# WH_Test_Station_Schematic_RevA.net
KiCad netlist of a schematic drawn in EasyEDA
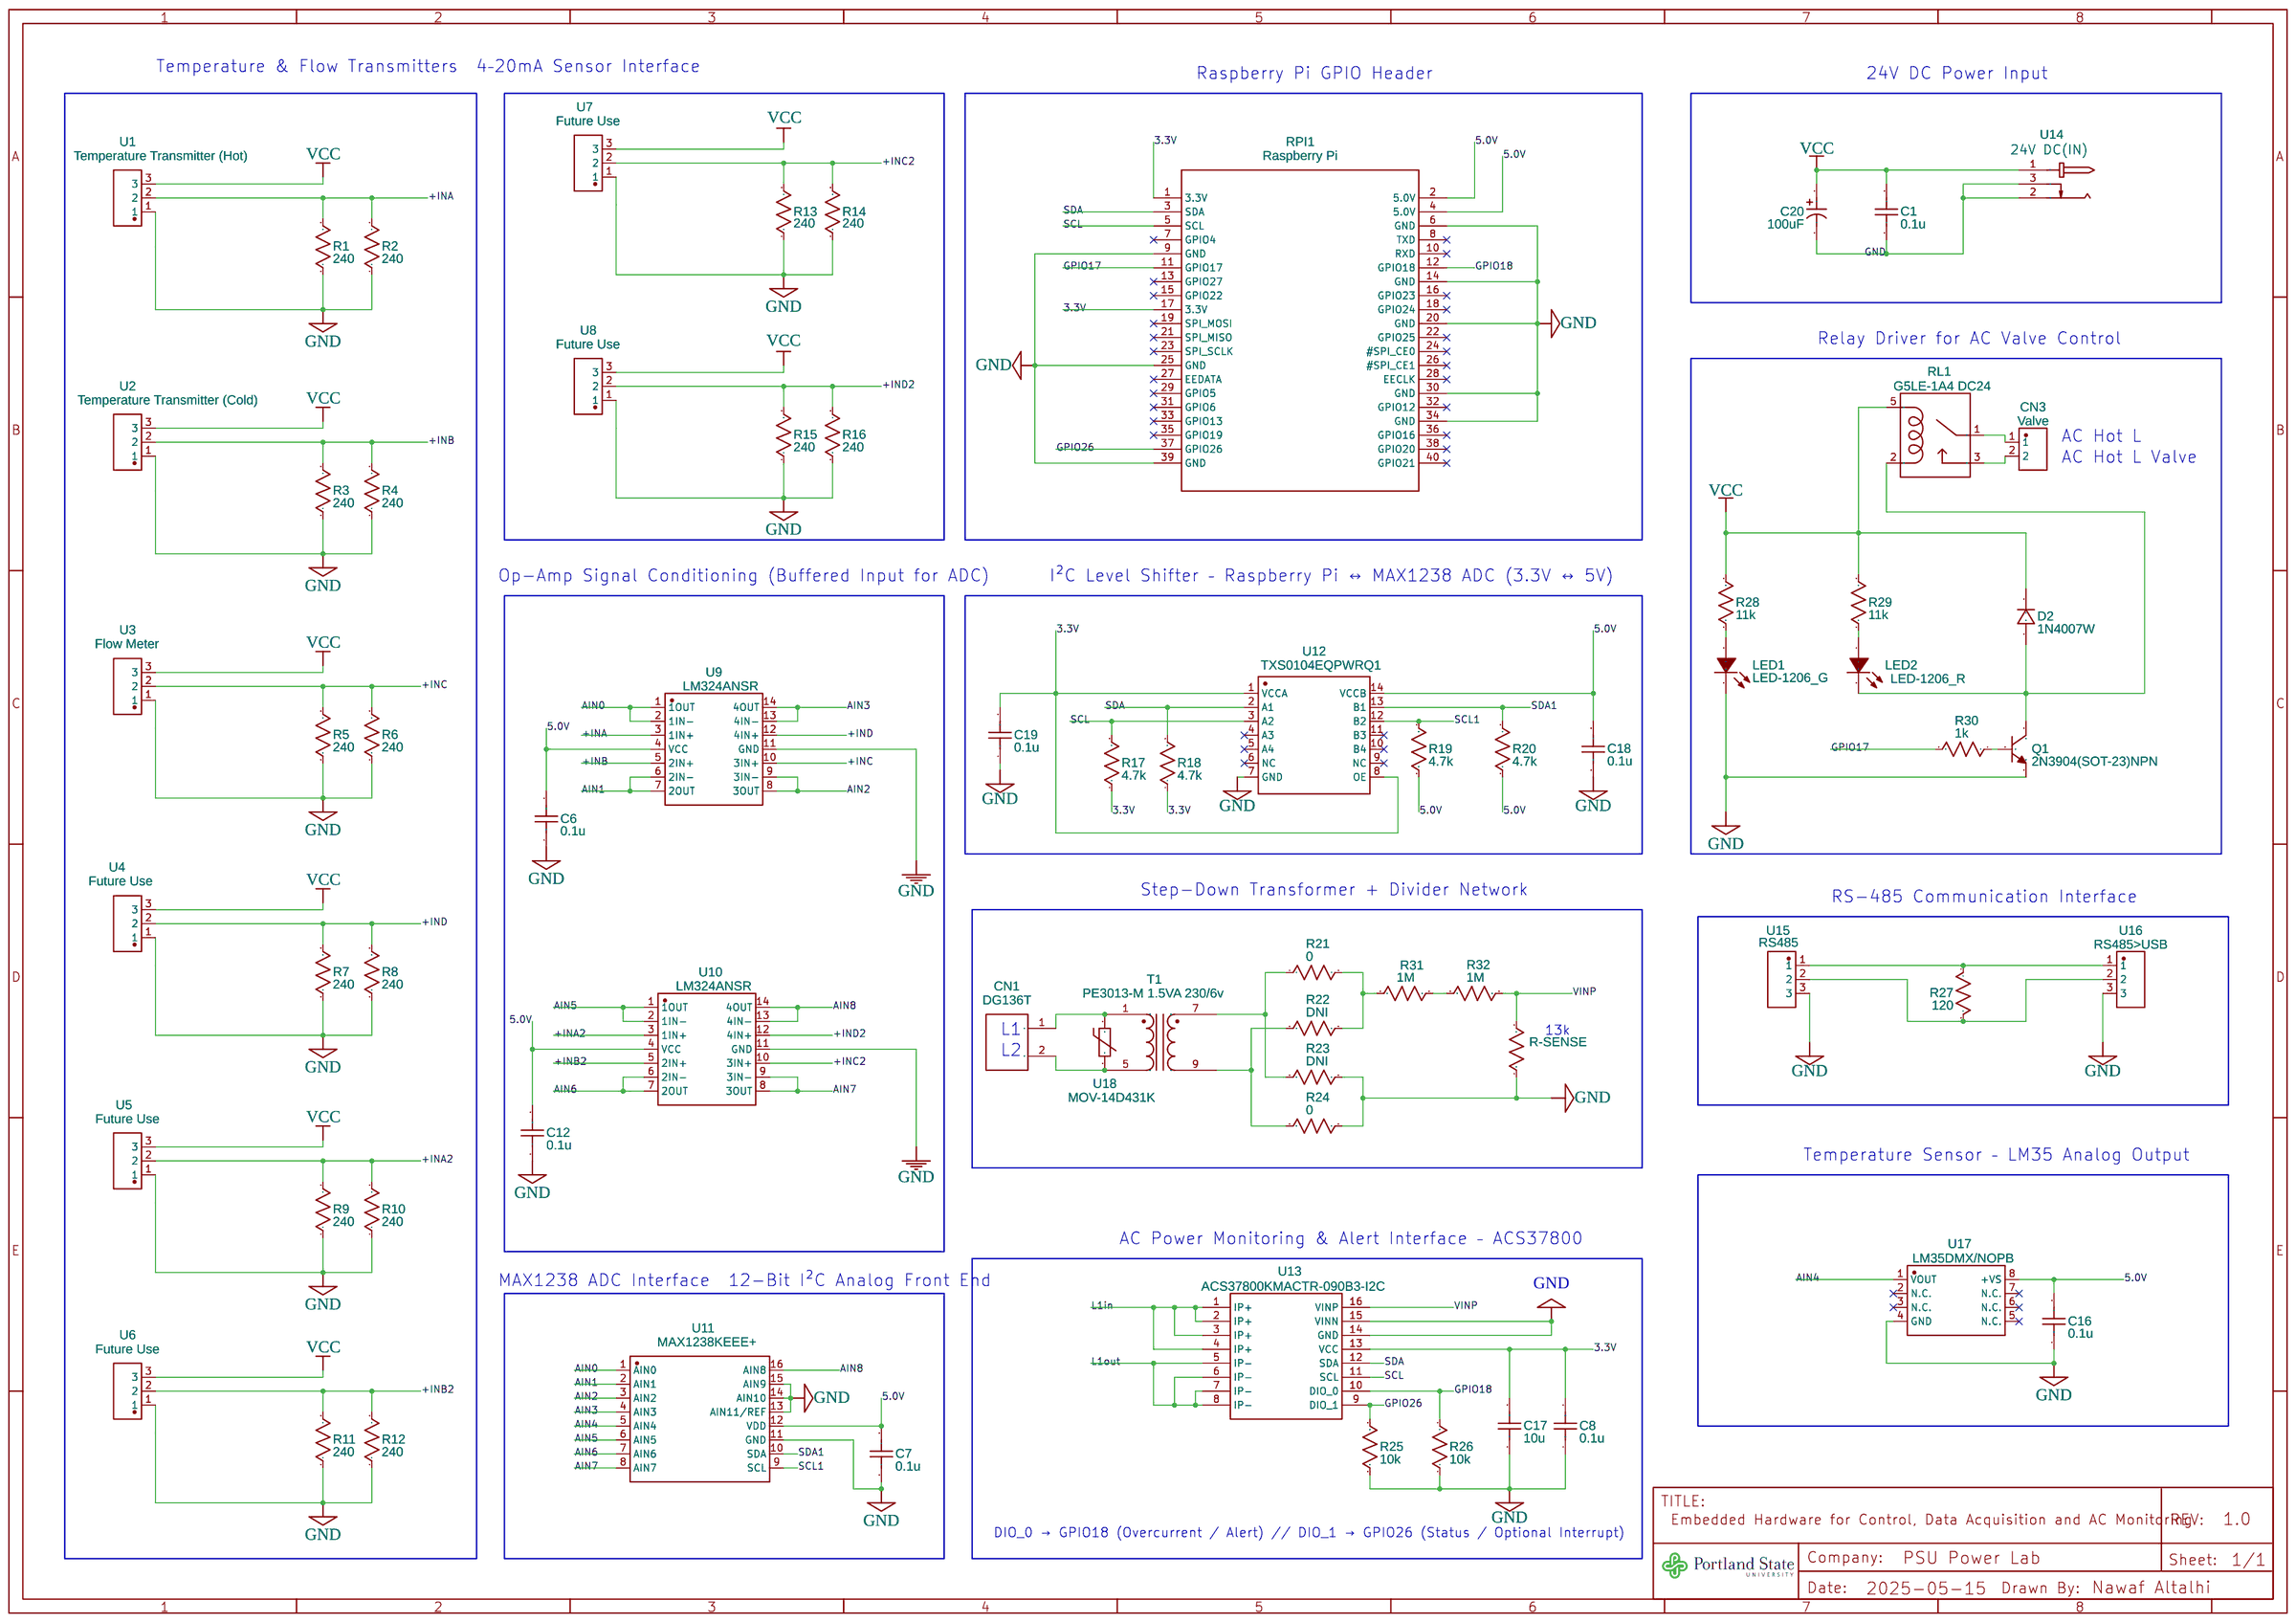
[diagram p0: schematic sheet]

(export (version "E")
  (design (tool "Eeschema 10.0.6"))
  (components
    (comp (ref "C1") (value "0.1u") (libsource (lib "") (part "C_0603_US")))
    (comp (ref "C6") (value "0.1u") (libsource (lib "") (part "C_0603_US")))
    (comp (ref "C7") (value "0.1u") (libsource (lib "") (part "C_0603_US")))
    (comp (ref "C8") (value "0.1u") (libsource (lib "") (part "C_0603_US")))
    (comp (ref "C12") (value "0.1u") (libsource (lib "") (part "C_0603_US")))
    (comp (ref "C16") (value "0.1u") (libsource (lib "") (part "C_0603_US")))
    (comp (ref "C17") (value "10u") (libsource (lib "") (part "C_0603_US")))
    (comp (ref "C18") (value "0.1u") (libsource (lib "") (part "C_0603_US")))
    (comp (ref "C19") (value "0.1u") (libsource (lib "") (part "C_0603_US")))
    (comp (ref "C20")
      (value "100uF")
      (fields (field (name "Manufacturer Part") "RVT1H101M0607") (field (name "Manufacturer") "ROQANG(容强)"))
      (libsource (lib "") (part "RVT1H101M0607"))
    )
    (comp (ref "CN1")
      (value "DG136T")
      (fields (field (name "Manufacturer Part") "Degson"))
      (libsource (lib "") (part "DG136T_2W_x12.7_Terminals"))
    )
    (comp (ref "CN3")
      (value "Valve")
      (fields
        (field (name "Manufacturer Part") "DBT50G-6.35-2P-BK-P OGC")
        (field (name "Manufacturer") "DORABO(地博电气)")
      )
      (libsource (lib "") (part "DBT50G-6.35-2P-BK-P OGC"))
    )
    (comp (ref "D2")
      (value "1N4007W")
      (fields (field (name "Manufacturer") "BLUE ROCKET"))
      (libsource (lib "") (part "1N4007W"))
    )
    (comp (ref "LED1")
      (value "LED-1206_G")
      (fields
        (field (name "Manufacturer Part") "19-217/GHC-YR1S2/3T")
        (field (name "Manufacturer") "EVERLIGHT(台湾亿光)")
      )
      (libsource (lib "") (part "LED-0603_G"))
    )
    (comp (ref "LED2")
      (value "LED-1206_R")
      (fields
        (field (name "Manufacturer Part") "19-217/R6C-AL1M2VY/3T")
        (field (name "Manufacturer") "EVERLIGHT(台湾亿光)")
      )
      (libsource (lib "") (part "LED-0603_R"))
    )
    (comp (ref "Q1")
      (value "2N3904(SOT-23)NPN")
      (fields (field (name "Manufacturer Part") "2n3904S-RTK/PS") (field (name "Manufacturer") "KEC"))
      (libsource (lib "") (part "2N3904(SOT-23)"))
    )
    (comp (ref "R-SENSE") (value "13k") (libsource (lib "") (part "R_0603_US_2")))
    (comp (ref "R1") (value "240") (libsource (lib "") (part "R_0603_US")))
    (comp (ref "R2") (value "240") (libsource (lib "") (part "R_0603_US")))
    (comp (ref "R3") (value "240") (libsource (lib "") (part "R_0603_US")))
    (comp (ref "R4") (value "240") (libsource (lib "") (part "R_0603_US")))
    (comp (ref "R5") (value "240") (libsource (lib "") (part "R_0603_US")))
    (comp (ref "R6") (value "240") (libsource (lib "") (part "R_0603_US")))
    (comp (ref "R7") (value "240") (libsource (lib "") (part "R_0603_US")))
    (comp (ref "R8") (value "240") (libsource (lib "") (part "R_0603_US")))
    (comp (ref "R9") (value "240") (libsource (lib "") (part "R_0603_US")))
    (comp (ref "R10") (value "240") (libsource (lib "") (part "R_0603_US")))
    (comp (ref "R11") (value "240") (libsource (lib "") (part "R_0603_US")))
    (comp (ref "R12") (value "240") (libsource (lib "") (part "R_0603_US")))
    (comp (ref "R13") (value "240") (libsource (lib "") (part "R_0603_US")))
    (comp (ref "R14") (value "240") (libsource (lib "") (part "R_0603_US")))
    (comp (ref "R15") (value "240") (libsource (lib "") (part "R_0603_US")))
    (comp (ref "R16") (value "240") (libsource (lib "") (part "R_0603_US")))
    (comp (ref "R17") (value "4.7k") (libsource (lib "") (part "R_0603_US")))
    (comp (ref "R18") (value "4.7k") (libsource (lib "") (part "R_0603_US")))
    (comp (ref "R19") (value "4.7k") (libsource (lib "") (part "R_0603_US")))
    (comp (ref "R20") (value "4.7k") (libsource (lib "") (part "R_0603_US")))
    (comp (ref "R21") (value "0") (libsource (lib "") (part "R_0603_US_1")))
    (comp (ref "R22") (value "DNI") (libsource (lib "") (part "R_0603_US_1")))
    (comp (ref "R23") (value "DNI") (libsource (lib "") (part "R_0603_US_1")))
    (comp (ref "R24") (value "0") (libsource (lib "") (part "R_0603_US_1")))
    (comp (ref "R25") (value "10k") (libsource (lib "") (part "R_0603_US")))
    (comp (ref "R26") (value "10k") (libsource (lib "") (part "R_0603_US")))
    (comp (ref "R27") (value "120") (libsource (lib "") (part "R_0603_US_3")))
    (comp (ref "R28") (value "11k") (libsource (lib "") (part "R_0603_US")))
    (comp (ref "R29") (value "11k") (libsource (lib "") (part "R_0603_US")))
    (comp (ref "R30") (value "1k") (libsource (lib "") (part "R_0603_US_4")))
    (comp (ref "R31") (value "1M") (libsource (lib "") (part "R_0603_US_1")))
    (comp (ref "R32") (value "1M") (libsource (lib "") (part "R_0603_US_1")))
    (comp (ref "RL1")
      (value "G5LE-1A4 DC24")
      (fields (field (name "Manufacturer") "OMRON(欧姆龙)"))
      (libsource (lib "") (part "G5LE-1A4 DC24"))
    )
    (comp (ref "RPI1") (value "Raspberry Pi") (libsource (lib "") (part "PiTFT 2.2")))
    (comp (ref "T1") (value "PE3013-M 1.5VA 230/6v") (libsource (lib "") (part "PE3013-M 1.5VA 230/6v")))
    (comp (ref "U1")
      (value "Temperature Transmitter (Hot)")
      (fields
        (field (name "Manufacturer Part") "DB301V-3.5-3P-GN-S")
        (field (name "Manufacturer") "DORABO(地博电气)")
      )
      (libsource (lib "") (part "DB301V-3.5-3P-GN_1"))
    )
    (comp (ref "U2")
      (value "Temperature Transmitter (Cold)")
      (fields
        (field (name "Manufacturer Part") "DB301V-3.5-3P-GN-S")
        (field (name "Manufacturer") "DORABO(地博电气)")
      )
      (libsource (lib "") (part "DB301V-3.5-3P-GN_1"))
    )
    (comp (ref "U3")
      (value "Flow Meter")
      (fields
        (field (name "Manufacturer Part") "DB301V-3.5-3P-GN-S")
        (field (name "Manufacturer") "DORABO(地博电气)")
      )
      (libsource (lib "") (part "DB301V-3.5-3P-GN_1"))
    )
    (comp (ref "U4")
      (value "Future Use")
      (fields
        (field (name "Manufacturer Part") "DB301V-3.5-3P-GN-S")
        (field (name "Manufacturer") "DORABO(地博电气)")
      )
      (libsource (lib "") (part "DB301V-3.5-3P-GN_1"))
    )
    (comp (ref "U5")
      (value "Future Use")
      (fields
        (field (name "Manufacturer Part") "DB301V-3.5-3P-GN-S")
        (field (name "Manufacturer") "DORABO(地博电气)")
      )
      (libsource (lib "") (part "DB301V-3.5-3P-GN_1"))
    )
    (comp (ref "U6")
      (value "Future Use")
      (fields
        (field (name "Manufacturer Part") "DB301V-3.5-3P-GN-S")
        (field (name "Manufacturer") "DORABO(地博电气)")
      )
      (libsource (lib "") (part "DB301V-3.5-3P-GN_1"))
    )
    (comp (ref "U7")
      (value "Future Use")
      (fields
        (field (name "Manufacturer Part") "DB301V-3.5-3P-GN-S")
        (field (name "Manufacturer") "DORABO(地博电气)")
      )
      (libsource (lib "") (part "DB301V-3.5-3P-GN_1"))
    )
    (comp (ref "U8")
      (value "Future Use")
      (fields
        (field (name "Manufacturer Part") "DB301V-3.5-3P-GN-S")
        (field (name "Manufacturer") "DORABO(地博电气)")
      )
      (libsource (lib "") (part "DB301V-3.5-3P-GN_1"))
    )
    (comp (ref "U9")
      (value "LM324ANSR")
      (fields (field (name "Manufacturer") "TI(德州仪器)"))
      (libsource (lib "") (part "LM324ANSR"))
    )
    (comp (ref "U10")
      (value "LM324ANSR")
      (fields (field (name "Manufacturer") "TI(德州仪器)"))
      (libsource (lib "") (part "LM324ANSR"))
    )
    (comp (ref "U11")
      (value "MAX1238KEEE+")
      (fields
        (field (name "Manufacturer Part") "MAX1239KEEE+")
        (field (name "Manufacturer") "ADI(亚德诺)/MAXIM(美信)")
      )
      (libsource (lib "") (part "MAX1239KEEE+"))
    )
    (comp (ref "U12")
      (value "TXS0104EQPWRQ1")
      (fields (field (name "Manufacturer") "TI(德州仪器)"))
      (libsource (lib "") (part "TXS0104EQPWRQ1"))
    )
    (comp (ref "U13")
      (value "ACS37800KMACTR-090B3-I2C")
      (fields
        (field (name "Manufacturer Part") "ACS37800KMACTR-030B3-I2C")
        (field (name "Manufacturer") "Allegro microsystems")
      )
      (libsource (lib "") (part "ACS37800KMACTR-030B3-I2C COPY"))
    )
    (comp (ref "U14")
      (value "24 V DC(IN)")
      (fields (field (name "Manufacturer Part") "XDJK-0051-025") (field (name "Manufacturer") "LX(连欣科技)"))
      (libsource (lib "") (part "XDJK-0051-025"))
    )
    (comp (ref "U15")
      (value "RS485")
      (fields
        (field (name "Manufacturer Part") "DB301V-3.5-3P-GN-S")
        (field (name "Manufacturer") "DORABO(地博电气)")
      )
      (libsource (lib "") (part "DB301V-3.5-3P-GN"))
    )
    (comp (ref "U16")
      (value "RS485>USB")
      (fields
        (field (name "Manufacturer Part") "DB301V-3.5-3P-GN-S")
        (field (name "Manufacturer") "DORABO(地博电气)")
      )
      (libsource (lib "") (part "DB301V-3.5-3P-GN_2"))
    )
    (comp (ref "U17")
      (value "LM35DMX/NOPB")
      (fields (field (name "Manufacturer") "TI(德州仪器)"))
      (libsource (lib "") (part "LM35DMX/NOPB"))
    )
    (comp (ref "U18")
      (value "MOV-14D431K")
      (fields (field (name "Manufacturer") "BOURNS"))
      (libsource (lib "") (part "MOV-14D431K"))
    )
  )
  (nets
    (net (code "1") (name "/+INA") (class "Default")
      (node (ref "R1") (pin "2") (pinfunction "2_2") (pintype "unspecified"))
      (node (ref "R2") (pin "2") (pinfunction "2_2") (pintype "unspecified"))
      (node (ref "U1") (pin "2") (pinfunction "2_2") (pintype "unspecified"))
      (node (ref "U9") (pin "3") (pinfunction "1IN+_3") (pintype "unspecified"))
    )
    (net (code "2") (name "/+INA2") (class "Default")
      (node (ref "R10") (pin "2") (pinfunction "2_2") (pintype "unspecified"))
      (node (ref "R9") (pin "2") (pinfunction "2_2") (pintype "unspecified"))
      (node (ref "U10") (pin "3") (pinfunction "1IN+_3") (pintype "unspecified"))
      (node (ref "U5") (pin "2") (pinfunction "2_2") (pintype "unspecified"))
    )
    (net (code "3") (name "/+INB") (class "Default")
      (node (ref "R3") (pin "2") (pinfunction "2_2") (pintype "unspecified"))
      (node (ref "R4") (pin "2") (pinfunction "2_2") (pintype "unspecified"))
      (node (ref "U2") (pin "2") (pinfunction "2_2") (pintype "unspecified"))
      (node (ref "U9") (pin "5") (pinfunction "2IN+_5") (pintype "unspecified"))
    )
    (net (code "4") (name "/+INB2") (class "Default")
      (node (ref "R11") (pin "2") (pinfunction "2_2") (pintype "unspecified"))
      (node (ref "R12") (pin "2") (pinfunction "2_2") (pintype "unspecified"))
      (node (ref "U10") (pin "5") (pinfunction "2IN+_5") (pintype "unspecified"))
      (node (ref "U6") (pin "2") (pinfunction "2_2") (pintype "unspecified"))
    )
    (net (code "5") (name "/+INC") (class "Default")
      (node (ref "R5") (pin "2") (pinfunction "2_2") (pintype "unspecified"))
      (node (ref "R6") (pin "2") (pinfunction "2_2") (pintype "unspecified"))
      (node (ref "U3") (pin "2") (pinfunction "2_2") (pintype "unspecified"))
      (node (ref "U9") (pin "10") (pinfunction "3IN+_10") (pintype "unspecified"))
    )
    (net (code "6") (name "/+INC2") (class "Default")
      (node (ref "R13") (pin "2") (pinfunction "2_2") (pintype "unspecified"))
      (node (ref "R14") (pin "2") (pinfunction "2_2") (pintype "unspecified"))
      (node (ref "U10") (pin "10") (pinfunction "3IN+_10") (pintype "unspecified"))
      (node (ref "U7") (pin "2") (pinfunction "2_2") (pintype "unspecified"))
    )
    (net (code "7") (name "/+IND") (class "Default")
      (node (ref "R7") (pin "2") (pinfunction "2_2") (pintype "unspecified"))
      (node (ref "R8") (pin "2") (pinfunction "2_2") (pintype "unspecified"))
      (node (ref "U4") (pin "2") (pinfunction "2_2") (pintype "unspecified"))
      (node (ref "U9") (pin "12") (pinfunction "4IN+_12") (pintype "unspecified"))
    )
    (net (code "8") (name "/+IND2") (class "Default")
      (node (ref "R15") (pin "2") (pinfunction "2_2") (pintype "unspecified"))
      (node (ref "R16") (pin "2") (pinfunction "2_2") (pintype "unspecified"))
      (node (ref "U10") (pin "12") (pinfunction "4IN+_12") (pintype "unspecified"))
      (node (ref "U8") (pin "2") (pinfunction "2_2") (pintype "unspecified"))
    )
    (net (code "9") (name "/3.3V") (class "Default")
      (node (ref "C17") (pin "2") (pinfunction "2_2") (pintype "unspecified"))
      (node (ref "C19") (pin "2") (pinfunction "2_2") (pintype "unspecified"))
      (node (ref "C8") (pin "2") (pinfunction "2_2") (pintype "unspecified"))
      (node (ref "R17") (pin "1") (pinfunction "1_1") (pintype "unspecified"))
      (node (ref "R18") (pin "1") (pinfunction "1_1") (pintype "unspecified"))
      (node (ref "RPI1") (pin "1") (pinfunction "3.3V_1") (pintype "unspecified"))
      (node (ref "RPI1") (pin "17") (pinfunction "3.3V_17") (pintype "unspecified"))
      (node (ref "U12") (pin "1") (pinfunction "VCCA_1") (pintype "unspecified"))
      (node (ref "U12") (pin "8") (pinfunction "OE_8") (pintype "unspecified"))
      (node (ref "U13") (pin "13") (pinfunction "VCC_13") (pintype "unspecified"))
    )
    (net (code "10") (name "/5.0V") (class "Default")
      (node (ref "C12") (pin "2") (pinfunction "2_2") (pintype "unspecified"))
      (node (ref "C16") (pin "2") (pinfunction "2_2") (pintype "unspecified"))
      (node (ref "C18") (pin "2") (pinfunction "2_2") (pintype "unspecified"))
      (node (ref "C6") (pin "2") (pinfunction "2_2") (pintype "unspecified"))
      (node (ref "C7") (pin "2") (pinfunction "2_2") (pintype "unspecified"))
      (node (ref "R19") (pin "1") (pinfunction "1_1") (pintype "unspecified"))
      (node (ref "R20") (pin "1") (pinfunction "1_1") (pintype "unspecified"))
      (node (ref "RPI1") (pin "2") (pinfunction "5.0V_2") (pintype "unspecified"))
      (node (ref "RPI1") (pin "4") (pinfunction "5.0V_4") (pintype "unspecified"))
      (node (ref "U10") (pin "4") (pinfunction "VCC_4") (pintype "unspecified"))
      (node (ref "U11") (pin "12") (pinfunction "VDD_12") (pintype "unspecified"))
      (node (ref "U12") (pin "14") (pinfunction "VCCB_14") (pintype "unspecified"))
      (node (ref "U17") (pin "8") (pinfunction "+VS_8") (pintype "unspecified"))
      (node (ref "U9") (pin "4") (pinfunction "VCC_4") (pintype "unspecified"))
    )
    (net (code "11") (name "/AIN0") (class "Default")
      (node (ref "U11") (pin "1") (pinfunction "AIN0_1") (pintype "unspecified"))
      (node (ref "U9") (pin "1") (pinfunction "1OUT_1") (pintype "unspecified"))
      (node (ref "U9") (pin "2") (pinfunction "1IN-_2") (pintype "unspecified"))
    )
    (net (code "12") (name "/AIN1") (class "Default")
      (node (ref "U11") (pin "2") (pinfunction "AIN1_2") (pintype "unspecified"))
      (node (ref "U9") (pin "6") (pinfunction "2IN-_6") (pintype "unspecified"))
      (node (ref "U9") (pin "7") (pinfunction "2OUT_7") (pintype "unspecified"))
    )
    (net (code "13") (name "/AIN2") (class "Default")
      (node (ref "U11") (pin "3") (pinfunction "AIN2_3") (pintype "unspecified"))
      (node (ref "U9") (pin "8") (pinfunction "3OUT_8") (pintype "unspecified"))
      (node (ref "U9") (pin "9") (pinfunction "3IN-_9") (pintype "unspecified"))
    )
    (net (code "14") (name "/AIN3") (class "Default")
      (node (ref "U11") (pin "4") (pinfunction "AIN3_4") (pintype "unspecified"))
      (node (ref "U9") (pin "13") (pinfunction "4IN-_13") (pintype "unspecified"))
      (node (ref "U9") (pin "14") (pinfunction "4OUT_14") (pintype "unspecified"))
    )
    (net (code "15") (name "/AIN4") (class "Default")
      (node (ref "U11") (pin "5") (pinfunction "AIN4_5") (pintype "unspecified"))
      (node (ref "U17") (pin "1") (pinfunction "VOUT_1") (pintype "unspecified"))
    )
    (net (code "16") (name "/AIN5") (class "Default")
      (node (ref "U10") (pin "1") (pinfunction "1OUT_1") (pintype "unspecified"))
      (node (ref "U10") (pin "2") (pinfunction "1IN-_2") (pintype "unspecified"))
      (node (ref "U11") (pin "6") (pinfunction "AIN5_6") (pintype "unspecified"))
    )
    (net (code "17") (name "/AIN6") (class "Default")
      (node (ref "U10") (pin "6") (pinfunction "2IN-_6") (pintype "unspecified"))
      (node (ref "U10") (pin "7") (pinfunction "2OUT_7") (pintype "unspecified"))
      (node (ref "U11") (pin "7") (pinfunction "AIN6_7") (pintype "unspecified"))
    )
    (net (code "18") (name "/AIN7") (class "Default")
      (node (ref "U10") (pin "8") (pinfunction "3OUT_8") (pintype "unspecified"))
      (node (ref "U10") (pin "9") (pinfunction "3IN-_9") (pintype "unspecified"))
      (node (ref "U11") (pin "8") (pinfunction "AIN7_8") (pintype "unspecified"))
    )
    (net (code "19") (name "/AIN8") (class "Default")
      (node (ref "U10") (pin "13") (pinfunction "4IN-_13") (pintype "unspecified"))
      (node (ref "U10") (pin "14") (pinfunction "4OUT_14") (pintype "unspecified"))
      (node (ref "U11") (pin "16") (pinfunction "AIN8_16") (pintype "unspecified"))
    )
    (net (code "20") (name "/GPIO17") (class "Default")
      (node (ref "R30") (pin "2") (pinfunction "2_2") (pintype "unspecified"))
      (node (ref "RPI1") (pin "11") (pinfunction "GPIO17_11") (pintype "unspecified"))
    )
    (net (code "21") (name "/GPIO18") (class "Default")
      (node (ref "R26") (pin "2") (pinfunction "2_2") (pintype "unspecified"))
      (node (ref "RPI1") (pin "12") (pinfunction "GPIO18_12") (pintype "unspecified"))
      (node (ref "U13") (pin "10") (pinfunction "DIO_0_10") (pintype "unspecified"))
    )
    (net (code "22") (name "/GPIO26") (class "Default")
      (node (ref "R25") (pin "2") (pinfunction "2_2") (pintype "unspecified"))
      (node (ref "RPI1") (pin "37") (pinfunction "GPIO26_37") (pintype "unspecified"))
      (node (ref "U13") (pin "9") (pinfunction "DIO_1_9") (pintype "unspecified"))
    )
    (net (code "23") (name "/L1in") (class "Default")
      (node (ref "U13") (pin "1") (pinfunction "IP+_1") (pintype "unspecified"))
      (node (ref "U13") (pin "2") (pinfunction "IP+_2") (pintype "unspecified"))
      (node (ref "U13") (pin "3") (pinfunction "IP+_3") (pintype "unspecified"))
      (node (ref "U13") (pin "4") (pinfunction "IP+_4") (pintype "unspecified"))
    )
    (net (code "24") (name "/L1out") (class "Default")
      (node (ref "U13") (pin "5") (pinfunction "IP-_5") (pintype "unspecified"))
      (node (ref "U13") (pin "6") (pinfunction "IP-_6") (pintype "unspecified"))
      (node (ref "U13") (pin "7") (pinfunction "IP-_7") (pintype "unspecified"))
      (node (ref "U13") (pin "8") (pinfunction "IP-_8") (pintype "unspecified"))
    )
    (net (code "25") (name "/SCL") (class "Default")
      (node (ref "R17") (pin "2") (pinfunction "2_2") (pintype "unspecified"))
      (node (ref "RPI1") (pin "5") (pinfunction "SCL_5") (pintype "unspecified"))
      (node (ref "U12") (pin "3") (pinfunction "A2_3") (pintype "unspecified"))
      (node (ref "U13") (pin "11") (pinfunction "SCL_11") (pintype "unspecified"))
    )
    (net (code "26") (name "/SCL1") (class "Default")
      (node (ref "R19") (pin "2") (pinfunction "2_2") (pintype "unspecified"))
      (node (ref "U11") (pin "9") (pinfunction "SCL_9") (pintype "unspecified"))
      (node (ref "U12") (pin "12") (pinfunction "B2_12") (pintype "unspecified"))
    )
    (net (code "27") (name "/SDA") (class "Default")
      (node (ref "R18") (pin "2") (pinfunction "2_2") (pintype "unspecified"))
      (node (ref "RPI1") (pin "3") (pinfunction "SDA_3") (pintype "unspecified"))
      (node (ref "U12") (pin "2") (pinfunction "A1_2") (pintype "unspecified"))
      (node (ref "U13") (pin "12") (pinfunction "SDA_12") (pintype "unspecified"))
    )
    (net (code "28") (name "/SDA1") (class "Default")
      (node (ref "R20") (pin "2") (pinfunction "2_2") (pintype "unspecified"))
      (node (ref "U11") (pin "10") (pinfunction "SDA_10") (pintype "unspecified"))
      (node (ref "U12") (pin "13") (pinfunction "B1_13") (pintype "unspecified"))
    )
    (net (code "29") (name "/VINP") (class "Default")
      (node (ref "R-SENSE") (pin "2") (pinfunction "2_2") (pintype "unspecified"))
      (node (ref "R32") (pin "2") (pinfunction "2_2") (pintype "unspecified"))
      (node (ref "U13") (pin "16") (pinfunction "VINP_16") (pintype "unspecified"))
    )
    (net (code "30") (name "GND") (class "Default")
      (node (ref "C1") (pin "1") (pinfunction "1_1") (pintype "unspecified"))
      (node (ref "C12") (pin "1") (pinfunction "1_1") (pintype "unspecified"))
      (node (ref "C16") (pin "1") (pinfunction "1_1") (pintype "unspecified"))
      (node (ref "C17") (pin "1") (pinfunction "1_1") (pintype "unspecified"))
      (node (ref "C18") (pin "1") (pinfunction "1_1") (pintype "unspecified"))
      (node (ref "C19") (pin "1") (pinfunction "1_1") (pintype "unspecified"))
      (node (ref "C20") (pin "2") (pinfunction "2_2") (pintype "input"))
      (node (ref "C6") (pin "1") (pinfunction "1_1") (pintype "unspecified"))
      (node (ref "C7") (pin "1") (pinfunction "1_1") (pintype "unspecified"))
      (node (ref "C8") (pin "1") (pinfunction "1_1") (pintype "unspecified"))
      (node (ref "LED1") (pin "2") (pinfunction "2_2") (pintype "unspecified"))
      (node (ref "Q1") (pin "1") (pinfunction "E_1") (pintype "input"))
      (node (ref "R-SENSE") (pin "1") (pinfunction "1_1") (pintype "unspecified"))
      (node (ref "R1") (pin "1") (pinfunction "1_1") (pintype "unspecified"))
      (node (ref "R10") (pin "1") (pinfunction "1_1") (pintype "unspecified"))
      (node (ref "R11") (pin "1") (pinfunction "1_1") (pintype "unspecified"))
      (node (ref "R12") (pin "1") (pinfunction "1_1") (pintype "unspecified"))
      (node (ref "R13") (pin "1") (pinfunction "1_1") (pintype "unspecified"))
      (node (ref "R14") (pin "1") (pinfunction "1_1") (pintype "unspecified"))
      (node (ref "R15") (pin "1") (pinfunction "1_1") (pintype "unspecified"))
      (node (ref "R16") (pin "1") (pinfunction "1_1") (pintype "unspecified"))
      (node (ref "R2") (pin "1") (pinfunction "1_1") (pintype "unspecified"))
      (node (ref "R23") (pin "2") (pinfunction "2_2") (pintype "unspecified"))
      (node (ref "R24") (pin "2") (pinfunction "2_2") (pintype "unspecified"))
      (node (ref "R25") (pin "1") (pinfunction "1_1") (pintype "unspecified"))
      (node (ref "R26") (pin "1") (pinfunction "1_1") (pintype "unspecified"))
      (node (ref "R3") (pin "1") (pinfunction "1_1") (pintype "unspecified"))
      (node (ref "R4") (pin "1") (pinfunction "1_1") (pintype "unspecified"))
      (node (ref "R5") (pin "1") (pinfunction "1_1") (pintype "unspecified"))
      (node (ref "R6") (pin "1") (pinfunction "1_1") (pintype "unspecified"))
      (node (ref "R7") (pin "1") (pinfunction "1_1") (pintype "unspecified"))
      (node (ref "R8") (pin "1") (pinfunction "1_1") (pintype "unspecified"))
      (node (ref "R9") (pin "1") (pinfunction "1_1") (pintype "unspecified"))
      (node (ref "RPI1") (pin "14") (pinfunction "GND_14") (pintype "unspecified"))
      (node (ref "RPI1") (pin "20") (pinfunction "GND_20") (pintype "unspecified"))
      (node (ref "RPI1") (pin "25") (pinfunction "GND_25") (pintype "unspecified"))
      (node (ref "RPI1") (pin "30") (pinfunction "GND_30") (pintype "unspecified"))
      (node (ref "RPI1") (pin "34") (pinfunction "GND_34") (pintype "unspecified"))
      (node (ref "RPI1") (pin "39") (pinfunction "GND_39") (pintype "unspecified"))
      (node (ref "RPI1") (pin "6") (pinfunction "GND_6") (pintype "unspecified"))
      (node (ref "RPI1") (pin "9") (pinfunction "GND_9") (pintype "unspecified"))
      (node (ref "U1") (pin "1") (pinfunction "1_1") (pintype "unspecified"))
      (node (ref "U10") (pin "11") (pinfunction "GND_11") (pintype "unspecified"))
      (node (ref "U11") (pin "11") (pinfunction "GND_11") (pintype "unspecified"))
      (node (ref "U11") (pin "13") (pinfunction "AIN11/REF_13") (pintype "unspecified"))
      (node (ref "U11") (pin "14") (pinfunction "AIN10_14") (pintype "unspecified"))
      (node (ref "U11") (pin "15") (pinfunction "AIN9_15") (pintype "unspecified"))
      (node (ref "U12") (pin "7") (pinfunction "GND_7") (pintype "unspecified"))
      (node (ref "U13") (pin "14") (pinfunction "GND_14") (pintype "unspecified"))
      (node (ref "U13") (pin "15") (pinfunction "VINN_15") (pintype "unspecified"))
      (node (ref "U14") (pin "2") (pinfunction "2_2") (pintype "unspecified"))
      (node (ref "U14") (pin "3") (pinfunction "3_3") (pintype "unspecified"))
      (node (ref "U15") (pin "3") (pinfunction "3_3") (pintype "unspecified"))
      (node (ref "U16") (pin "3") (pinfunction "3_3") (pintype "unspecified"))
      (node (ref "U17") (pin "4") (pinfunction "GND_4") (pintype "unspecified"))
      (node (ref "U2") (pin "1") (pinfunction "1_1") (pintype "unspecified"))
      (node (ref "U3") (pin "1") (pinfunction "1_1") (pintype "unspecified"))
      (node (ref "U4") (pin "1") (pinfunction "1_1") (pintype "unspecified"))
      (node (ref "U5") (pin "1") (pinfunction "1_1") (pintype "unspecified"))
      (node (ref "U6") (pin "1") (pinfunction "1_1") (pintype "unspecified"))
      (node (ref "U7") (pin "1") (pinfunction "1_1") (pintype "unspecified"))
      (node (ref "U8") (pin "1") (pinfunction "1_1") (pintype "unspecified"))
      (node (ref "U9") (pin "11") (pinfunction "GND_11") (pintype "unspecified"))
    )
    (net (code "31") (name "Net-(LED1-Pad1)") (class "Default")
      (node (ref "LED1") (pin "1") (pinfunction "1_1") (pintype "unspecified"))
      (node (ref "R28") (pin "1") (pinfunction "1_1") (pintype "unspecified"))
    )
    (net (code "32") (name "Net-(LED2-Pad1)") (class "Default")
      (node (ref "LED2") (pin "1") (pinfunction "1_1") (pintype "unspecified"))
      (node (ref "R29") (pin "1") (pinfunction "1_1") (pintype "unspecified"))
    )
    (net (code "33") (name "Net-(Q1-B)") (class "Default")
      (node (ref "Q1") (pin "2") (pinfunction "B_2") (pintype "input"))
      (node (ref "R30") (pin "1") (pinfunction "1_1") (pintype "unspecified"))
    )
    (net (code "34") (name "Net-(Q1-C)") (class "Default")
      (node (ref "D2") (pin "2") (pinfunction "2_2") (pintype "unspecified"))
      (node (ref "LED2") (pin "2") (pinfunction "2_2") (pintype "unspecified"))
      (node (ref "Q1") (pin "3") (pinfunction "C_3") (pintype "input"))
      (node (ref "RL1") (pin "2") (pinfunction "COIL2_2") (pintype "unspecified"))
    )
    (net (code "35") (name "Net-(R21-Pad2)") (class "Default")
      (node (ref "R21") (pin "2") (pinfunction "2_2") (pintype "unspecified"))
      (node (ref "R22") (pin "2") (pinfunction "2_2") (pintype "unspecified"))
      (node (ref "R31") (pin "1") (pinfunction "1_1") (pintype "unspecified"))
    )
    (net (code "36") (name "Net-(R27-Pad1)") (class "Default")
      (node (ref "R27") (pin "1") (pinfunction "1_1") (pintype "unspecified"))
      (node (ref "U15") (pin "1") (pinfunction "1_1") (pintype "unspecified"))
      (node (ref "U16") (pin "1") (pinfunction "1_1") (pintype "unspecified"))
    )
    (net (code "37") (name "Net-(R27-Pad2)") (class "Default")
      (node (ref "R27") (pin "2") (pinfunction "2_2") (pintype "unspecified"))
      (node (ref "U15") (pin "2") (pinfunction "2_2") (pintype "unspecified"))
      (node (ref "U16") (pin "2") (pinfunction "2_2") (pintype "unspecified"))
    )
    (net (code "38") (name "Net-(R31-Pad2)") (class "Default")
      (node (ref "R31") (pin "2") (pinfunction "2_2") (pintype "unspecified"))
      (node (ref "R32") (pin "1") (pinfunction "1_1") (pintype "unspecified"))
    )
    (net (code "39") (name "Net-(RL1-MAIN)") (class "Default")
      (node (ref "CN3") (pin "1") (pinfunction "1_1") (pintype "unspecified"))
      (node (ref "RL1") (pin "1") (pinfunction "MAIN_1") (pintype "unspecified"))
    )
    (net (code "40") (name "Net-(RL1-NO)") (class "Default")
      (node (ref "CN3") (pin "2") (pinfunction "2_2") (pintype "unspecified"))
      (node (ref "RL1") (pin "3") (pinfunction "NO_3") (pintype "unspecified"))
    )
    (net (code "41") (name "Net-(T1-PA)") (class "Default")
      (node (ref "CN1") (pin "1") (pinfunction "1_1") (pintype "unspecified"))
      (node (ref "T1") (pin "1") (pinfunction "PA_1") (pintype "unspecified"))
      (node (ref "U18") (pin "1") (pinfunction "1_1") (pintype "unspecified"))
    )
    (net (code "42") (name "Net-(T1-PB)") (class "Default")
      (node (ref "CN1") (pin "2") (pinfunction "2_2") (pintype "unspecified"))
      (node (ref "T1") (pin "5") (pinfunction "PB_5") (pintype "unspecified"))
      (node (ref "U18") (pin "2") (pinfunction "2_2") (pintype "unspecified"))
    )
    (net (code "43") (name "Net-(T1-SA)") (class "Default")
      (node (ref "R21") (pin "1") (pinfunction "1_1") (pintype "unspecified"))
      (node (ref "R23") (pin "1") (pinfunction "1_1") (pintype "unspecified"))
      (node (ref "T1") (pin "7") (pinfunction "SA_7") (pintype "unspecified"))
    )
    (net (code "44") (name "Net-(T1-SB)") (class "Default")
      (node (ref "R22") (pin "1") (pinfunction "1_1") (pintype "unspecified"))
      (node (ref "R24") (pin "1") (pinfunction "1_1") (pintype "unspecified"))
      (node (ref "T1") (pin "9") (pinfunction "SB_9") (pintype "unspecified"))
    )
    (net (code "45") (name "VCC") (class "Default")
      (node (ref "C1") (pin "2") (pinfunction "2_2") (pintype "unspecified"))
      (node (ref "C20") (pin "1") (pinfunction "1_1") (pintype "input"))
      (node (ref "D2") (pin "1") (pinfunction "1_1") (pintype "unspecified"))
      (node (ref "R28") (pin "2") (pinfunction "2_2") (pintype "unspecified"))
      (node (ref "R29") (pin "2") (pinfunction "2_2") (pintype "unspecified"))
      (node (ref "RL1") (pin "5") (pinfunction "COIL1_5") (pintype "unspecified"))
      (node (ref "U1") (pin "3") (pinfunction "3_3") (pintype "unspecified"))
      (node (ref "U14") (pin "1") (pinfunction "1_1") (pintype "unspecified"))
      (node (ref "U2") (pin "3") (pinfunction "3_3") (pintype "unspecified"))
      (node (ref "U3") (pin "3") (pinfunction "3_3") (pintype "unspecified"))
      (node (ref "U4") (pin "3") (pinfunction "3_3") (pintype "unspecified"))
      (node (ref "U5") (pin "3") (pinfunction "3_3") (pintype "unspecified"))
      (node (ref "U6") (pin "3") (pinfunction "3_3") (pintype "unspecified"))
      (node (ref "U7") (pin "3") (pinfunction "3_3") (pintype "unspecified"))
      (node (ref "U8") (pin "3") (pinfunction "3_3") (pintype "unspecified"))
    )
    (net (code "46") (name "unconnected-(RPI1-#SPI_CE0-Pad24)") (class "Default")
      (node (ref "RPI1") (pin "24") (pinfunction "#SPI_CE0_24") (pintype "unspecified+no_connect"))
    )
    (net (code "47") (name "unconnected-(RPI1-#SPI_CE1-Pad26)") (class "Default")
      (node (ref "RPI1") (pin "26") (pinfunction "#SPI_CE1_26") (pintype "unspecified+no_connect"))
    )
    (net (code "48") (name "unconnected-(RPI1-EECLK-Pad28)") (class "Default")
      (node (ref "RPI1") (pin "28") (pinfunction "EECLK_28") (pintype "unspecified+no_connect"))
    )
    (net (code "49") (name "unconnected-(RPI1-EEDATA-Pad27)") (class "Default")
      (node (ref "RPI1") (pin "27") (pinfunction "EEDATA_27") (pintype "unspecified+no_connect"))
    )
    (net (code "50") (name "unconnected-(RPI1-GPIO4-Pad7)") (class "Default")
      (node (ref "RPI1") (pin "7") (pinfunction "GPIO4_7") (pintype "unspecified+no_connect"))
    )
    (net (code "51") (name "unconnected-(RPI1-GPIO5-Pad29)") (class "Default")
      (node (ref "RPI1") (pin "29") (pinfunction "GPIO5_29") (pintype "unspecified+no_connect"))
    )
    (net (code "52") (name "unconnected-(RPI1-GPIO6-Pad31)") (class "Default")
      (node (ref "RPI1") (pin "31") (pinfunction "GPIO6_31") (pintype "unspecified+no_connect"))
    )
    (net (code "53") (name "unconnected-(RPI1-GPIO12-Pad32)") (class "Default")
      (node (ref "RPI1") (pin "32") (pinfunction "GPIO12_32") (pintype "unspecified+no_connect"))
    )
    (net (code "54") (name "unconnected-(RPI1-GPIO13-Pad33)") (class "Default")
      (node (ref "RPI1") (pin "33") (pinfunction "GPIO13_33") (pintype "unspecified+no_connect"))
    )
    (net (code "55") (name "unconnected-(RPI1-GPIO16-Pad36)") (class "Default")
      (node (ref "RPI1") (pin "36") (pinfunction "GPIO16_36") (pintype "unspecified+no_connect"))
    )
    (net (code "56") (name "unconnected-(RPI1-GPIO19-Pad35)") (class "Default")
      (node (ref "RPI1") (pin "35") (pinfunction "GPIO19_35") (pintype "unspecified+no_connect"))
    )
    (net (code "57") (name "unconnected-(RPI1-GPIO20-Pad38)") (class "Default")
      (node (ref "RPI1") (pin "38") (pinfunction "GPIO20_38") (pintype "unspecified+no_connect"))
    )
    (net (code "58") (name "unconnected-(RPI1-GPIO21-Pad40)") (class "Default")
      (node (ref "RPI1") (pin "40") (pinfunction "GPIO21_40") (pintype "unspecified+no_connect"))
    )
    (net (code "59") (name "unconnected-(RPI1-GPIO22-Pad15)") (class "Default")
      (node (ref "RPI1") (pin "15") (pinfunction "GPIO22_15") (pintype "unspecified+no_connect"))
    )
    (net (code "60") (name "unconnected-(RPI1-GPIO23-Pad16)") (class "Default")
      (node (ref "RPI1") (pin "16") (pinfunction "GPIO23_16") (pintype "unspecified+no_connect"))
    )
    (net (code "61") (name "unconnected-(RPI1-GPIO24-Pad18)") (class "Default")
      (node (ref "RPI1") (pin "18") (pinfunction "GPIO24_18") (pintype "unspecified+no_connect"))
    )
    (net (code "62") (name "unconnected-(RPI1-GPIO25-Pad22)") (class "Default")
      (node (ref "RPI1") (pin "22") (pinfunction "GPIO25_22") (pintype "unspecified+no_connect"))
    )
    (net (code "63") (name "unconnected-(RPI1-GPIO27-Pad13)") (class "Default")
      (node (ref "RPI1") (pin "13") (pinfunction "GPIO27_13") (pintype "unspecified+no_connect"))
    )
    (net (code "64") (name "unconnected-(RPI1-RXD-Pad10)") (class "Default")
      (node (ref "RPI1") (pin "10") (pinfunction "RXD_10") (pintype "unspecified+no_connect"))
    )
    (net (code "65") (name "unconnected-(RPI1-SPI_MISO-Pad21)") (class "Default")
      (node (ref "RPI1") (pin "21") (pinfunction "SPI_MISO_21") (pintype "unspecified+no_connect"))
    )
    (net (code "66") (name "unconnected-(RPI1-SPI_MOSI-Pad19)") (class "Default")
      (node (ref "RPI1") (pin "19") (pinfunction "SPI_MOSI_19") (pintype "unspecified+no_connect"))
    )
    (net (code "67") (name "unconnected-(RPI1-SPI_SCLK-Pad23)") (class "Default")
      (node (ref "RPI1") (pin "23") (pinfunction "SPI_SCLK_23") (pintype "unspecified+no_connect"))
    )
    (net (code "68") (name "unconnected-(RPI1-TXD-Pad8)") (class "Default")
      (node (ref "RPI1") (pin "8") (pinfunction "TXD_8") (pintype "output+no_connect"))
    )
    (net (code "69") (name "unconnected-(U12-A3-Pad4)") (class "Default")
      (node (ref "U12") (pin "4") (pinfunction "A3_4") (pintype "unspecified+no_connect"))
    )
    (net (code "70") (name "unconnected-(U12-A4-Pad5)") (class "Default")
      (node (ref "U12") (pin "5") (pinfunction "A4_5") (pintype "unspecified+no_connect"))
    )
    (net (code "71") (name "unconnected-(U12-B3-Pad11)") (class "Default")
      (node (ref "U12") (pin "11") (pinfunction "B3_11") (pintype "unspecified+no_connect"))
    )
    (net (code "72") (name "unconnected-(U12-B4-Pad10)") (class "Default")
      (node (ref "U12") (pin "10") (pinfunction "B4_10") (pintype "unspecified+no_connect"))
    )
    (net (code "73") (name "unconnected-(U12-NC-Pad6)") (class "Default")
      (node (ref "U12") (pin "6") (pinfunction "NC_6") (pintype "unspecified+no_connect"))
    )
    (net (code "74") (name "unconnected-(U12-NC-Pad9)") (class "Default")
      (node (ref "U12") (pin "9") (pinfunction "NC_9") (pintype "unspecified+no_connect"))
    )
    (net (code "75") (name "unconnected-(U17-N.C.-Pad2)") (class "Default")
      (node (ref "U17") (pin "2") (pinfunction "N.C._2") (pintype "unspecified+no_connect"))
    )
    (net (code "76") (name "unconnected-(U17-N.C.-Pad3)") (class "Default")
      (node (ref "U17") (pin "3") (pinfunction "N.C._3") (pintype "unspecified+no_connect"))
    )
    (net (code "77") (name "unconnected-(U17-N.C.-Pad5)") (class "Default")
      (node (ref "U17") (pin "5") (pinfunction "N.C._5") (pintype "unspecified+no_connect"))
    )
    (net (code "78") (name "unconnected-(U17-N.C.-Pad6)") (class "Default")
      (node (ref "U17") (pin "6") (pinfunction "N.C._6") (pintype "unspecified+no_connect"))
    )
    (net (code "79") (name "unconnected-(U17-N.C.-Pad7)") (class "Default")
      (node (ref "U17") (pin "7") (pinfunction "N.C._7") (pintype "unspecified+no_connect"))
    )
  )
)
